# inputs.net
KiCad netlist of a schematic drawn in Altium Designer
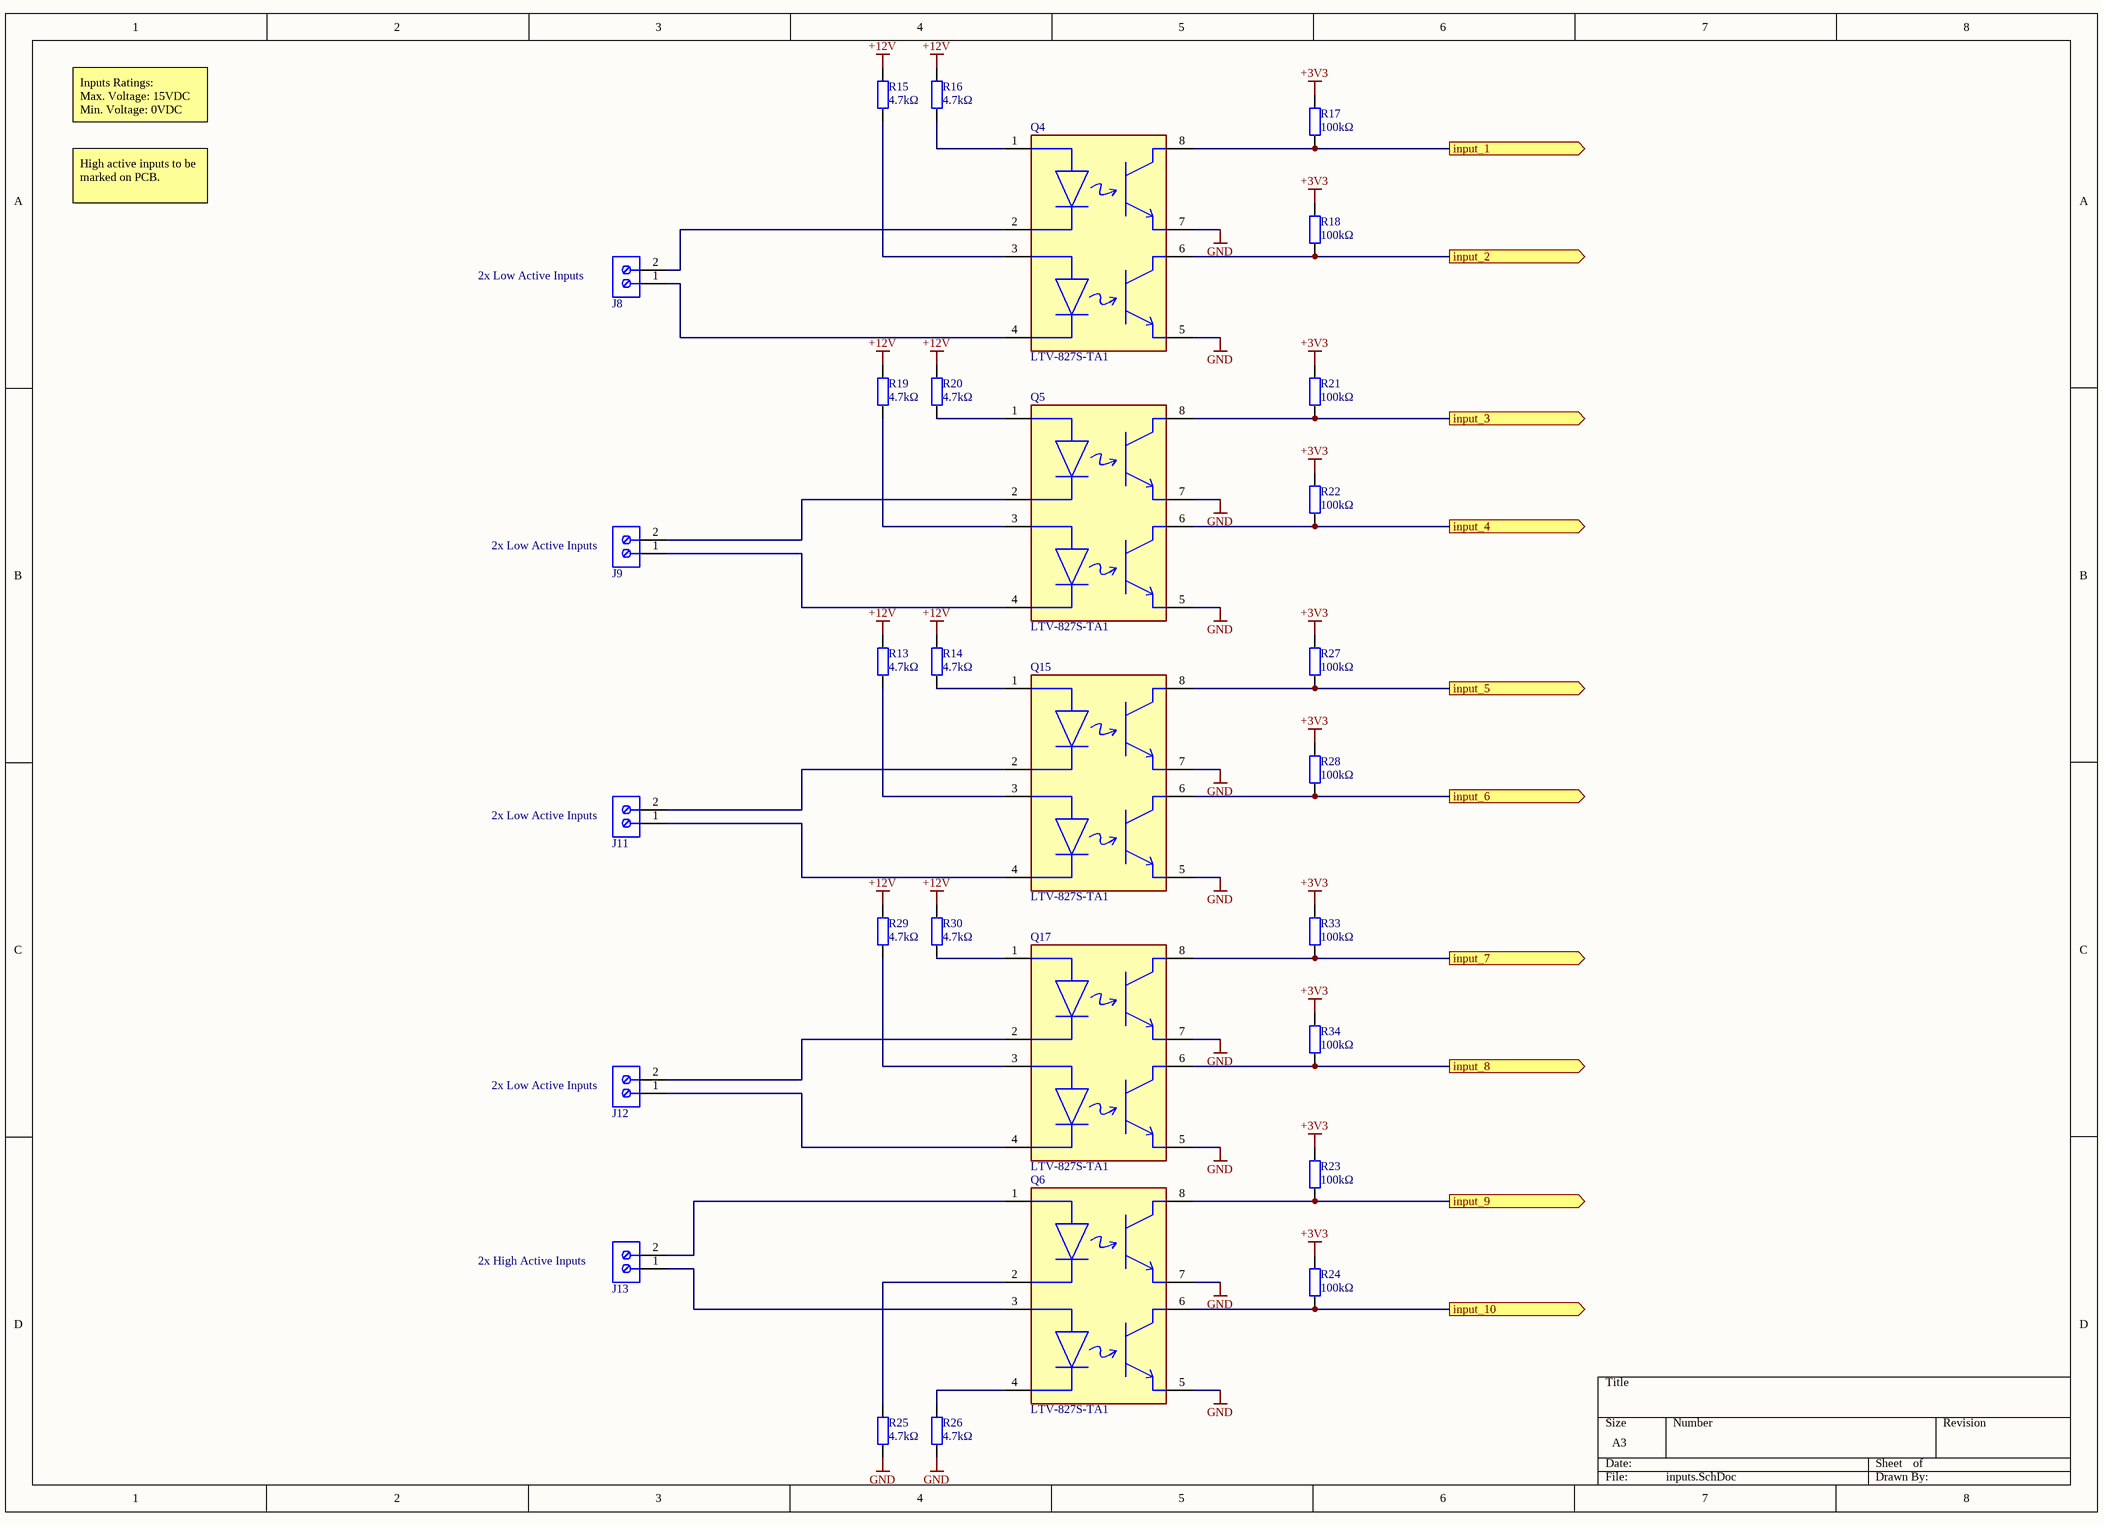
[diagram p0: inputs.SchDoc]

(export (version "E")
  (design (tool "Eeschema 10.0.6"))
  (components
    (comp (ref "J8")
      (value "282836-2")
      (footprint "TECO-282836-2_V")
      (description "Female Header, Pitch 5 mm, 1 x 2 Position, Height 10 mm, Tail Length 3.5 mm, Rohs, Bulk")
      (fields (field (name "VOLTAGE") "300V") (field (name "MANUFACTURER") "TE Connectivity"))
      (libsource (lib "Altium Content Vault") (part "CN-1P-F-TB2"))
    )
    (comp (ref "J9")
      (value "282836-2")
      (footprint "TECO-282836-2_V")
      (description "Female Header, Pitch 5 mm, 1 x 2 Position, Height 10 mm, Tail Length 3.5 mm, Rohs, Bulk")
      (fields (field (name "VOLTAGE") "300V") (field (name "MANUFACTURER") "TE Connectivity"))
      (libsource (lib "Altium Content Vault") (part "CN-1P-F-TB2"))
    )
    (comp (ref "J11")
      (value "282836-2")
      (footprint "TECO-282836-2_V")
      (description "Female Header, Pitch 5 mm, 1 x 2 Position, Height 10 mm, Tail Length 3.5 mm, Rohs, Bulk")
      (fields (field (name "VOLTAGE") "300V") (field (name "MANUFACTURER") "TE Connectivity"))
      (libsource (lib "Altium Content Vault") (part "CN-1P-F-TB2"))
    )
    (comp (ref "J12")
      (value "282836-2")
      (footprint "TECO-282836-2_V")
      (description "Female Header, Pitch 5 mm, 1 x 2 Position, Height 10 mm, Tail Length 3.5 mm, Rohs, Bulk")
      (fields (field (name "VOLTAGE") "300V") (field (name "MANUFACTURER") "TE Connectivity"))
      (libsource (lib "Altium Content Vault") (part "CN-1P-F-TB2"))
    )
    (comp (ref "J13")
      (value "282836-2")
      (footprint "TECO-282836-2_V")
      (description "Female Header, Pitch 5 mm, 1 x 2 Position, Height 10 mm, Tail Length 3.5 mm, Rohs, Bulk")
      (fields (field (name "VOLTAGE") "300V") (field (name "MANUFACTURER") "TE Connectivity"))
      (libsource (lib "Altium Content Vault") (part "CN-1P-F-TB2"))
    )
    (comp (ref "Q4")
      (value "LTV-827S-TA1")
      (footprint "FP-LTV-827S-TA1-MFG")
      (description "OPTOISOLATOR 5KV 2CH TRANS 8-SMD")
      (libsource (lib "Altium Content Vault") (part "7b7d251853f36bb38206e775f4a8ee5"))
    )
    (comp (ref "Q5")
      (value "LTV-827S-TA1")
      (footprint "FP-LTV-827S-TA1-MFG")
      (description "OPTOISOLATOR 5KV 2CH TRANS 8-SMD")
      (libsource (lib "Altium Content Vault") (part "7b7d251853f36bb38206e775f4a8ee5"))
    )
    (comp (ref "Q6")
      (value "LTV-827S-TA1")
      (footprint "FP-LTV-827S-TA1-MFG")
      (description "OPTOISOLATOR 5KV 2CH TRANS 8-SMD")
      (libsource (lib "Altium Content Vault") (part "7b7d251853f36bb38206e775f4a8ee5"))
    )
    (comp (ref "Q15")
      (value "LTV-827S-TA1")
      (footprint "FP-LTV-827S-TA1-MFG")
      (description "OPTOISOLATOR 5KV 2CH TRANS 8-SMD")
      (libsource (lib "Altium Content Vault") (part "7b7d251853f36bb38206e775f4a8ee5"))
    )
    (comp (ref "Q17")
      (value "LTV-827S-TA1")
      (footprint "FP-LTV-827S-TA1-MFG")
      (description "OPTOISOLATOR 5KV 2CH TRANS 8-SMD")
      (libsource (lib "Altium Content Vault") (part "7b7d251853f36bb38206e775f4a8ee5"))
    )
    (comp (ref "R13")
      (value "4.7kΩ")
      (footprint "RESC2013X50X30ML20T20")
      (description "Resistor")
      (libsource (lib "PCB_Project") (part "Res_0805"))
    )
    (comp (ref "R14")
      (value "4.7kΩ")
      (footprint "RESC2013X50X30ML20T20")
      (description "Resistor")
      (libsource (lib "PCB_Project") (part "Res_0805"))
    )
    (comp (ref "R15")
      (value "4.7kΩ")
      (footprint "RESC2013X50X30ML20T20")
      (description "Resistor")
      (libsource (lib "PCB_Project") (part "Res_0805"))
    )
    (comp (ref "R16")
      (value "4.7kΩ")
      (footprint "RESC2013X50X30ML20T20")
      (description "Resistor")
      (libsource (lib "PCB_Project") (part "Res_0805"))
    )
    (comp (ref "R17")
      (value "100kΩ")
      (footprint "RESC2013X50X30ML20T20")
      (description "Resistor")
      (libsource (lib "") (part "Res_0805_1"))
    )
    (comp (ref "R18")
      (value "100kΩ")
      (footprint "RESC2013X50X30ML20T20")
      (description "Resistor")
      (libsource (lib "") (part "Res_0805_1"))
    )
    (comp (ref "R19")
      (value "4.7kΩ")
      (footprint "RESC2013X50X30ML20T20")
      (description "Resistor")
      (libsource (lib "PCB_Project") (part "Res_0805"))
    )
    (comp (ref "R20")
      (value "4.7kΩ")
      (footprint "RESC2013X50X30ML20T20")
      (description "Resistor")
      (libsource (lib "PCB_Project") (part "Res_0805"))
    )
    (comp (ref "R21")
      (value "100kΩ")
      (footprint "RESC2013X50X30ML20T20")
      (description "Resistor")
      (libsource (lib "") (part "Res_0805_1"))
    )
    (comp (ref "R22")
      (value "100kΩ")
      (footprint "RESC2013X50X30ML20T20")
      (description "Resistor")
      (libsource (lib "") (part "Res_0805_1"))
    )
    (comp (ref "R23")
      (value "100kΩ")
      (footprint "RESC2013X50X30ML20T20")
      (description "Resistor")
      (libsource (lib "") (part "Res_0805_1"))
    )
    (comp (ref "R24")
      (value "100kΩ")
      (footprint "RESC2013X50X30ML20T20")
      (description "Resistor")
      (libsource (lib "") (part "Res_0805_1"))
    )
    (comp (ref "R25")
      (value "4.7kΩ")
      (footprint "RESC2013X50X30ML20T20")
      (description "Resistor")
      (libsource (lib "") (part "Res_0805_1"))
    )
    (comp (ref "R26")
      (value "4.7kΩ")
      (footprint "RESC2013X50X30ML20T20")
      (description "Resistor")
      (libsource (lib "") (part "Res_0805_1"))
    )
    (comp (ref "R27")
      (value "100kΩ")
      (footprint "RESC2013X50X30ML20T20")
      (description "Resistor")
      (libsource (lib "") (part "Res_0805_1"))
    )
    (comp (ref "R28")
      (value "100kΩ")
      (footprint "RESC2013X50X30ML20T20")
      (description "Resistor")
      (libsource (lib "") (part "Res_0805_1"))
    )
    (comp (ref "R29")
      (value "4.7kΩ")
      (footprint "RESC2013X50X30ML20T20")
      (description "Resistor")
      (libsource (lib "PCB_Project") (part "Res_0805"))
    )
    (comp (ref "R30")
      (value "4.7kΩ")
      (footprint "RESC2013X50X30ML20T20")
      (description "Resistor")
      (libsource (lib "PCB_Project") (part "Res_0805"))
    )
    (comp (ref "R33")
      (value "100kΩ")
      (footprint "RESC2013X50X30ML20T20")
      (description "Resistor")
      (libsource (lib "") (part "Res_0805_1"))
    )
    (comp (ref "R34")
      (value "100kΩ")
      (footprint "RESC2013X50X30ML20T20")
      (description "Resistor")
      (libsource (lib "") (part "Res_0805_1"))
    )
  )
  (nets
    (net (code "1") (name "+3V3") (class "Default")
      (node (ref "R17") (pin "1") (pinfunction "1_1") (pintype "passive"))
      (node (ref "R18") (pin "1") (pinfunction "1_1") (pintype "passive"))
      (node (ref "R21") (pin "1") (pinfunction "1_1") (pintype "passive"))
      (node (ref "R22") (pin "1") (pinfunction "1_1") (pintype "passive"))
      (node (ref "R23") (pin "1") (pinfunction "1_1") (pintype "passive"))
      (node (ref "R24") (pin "1") (pinfunction "1_1") (pintype "passive"))
      (node (ref "R27") (pin "1") (pinfunction "1_1") (pintype "passive"))
      (node (ref "R28") (pin "1") (pinfunction "1_1") (pintype "passive"))
      (node (ref "R33") (pin "1") (pinfunction "1_1") (pintype "passive"))
      (node (ref "R34") (pin "1") (pinfunction "1_1") (pintype "passive"))
    )
    (net (code "2") (name "+12V") (class "Default")
      (node (ref "R13") (pin "1") (pinfunction "1_1") (pintype "passive"))
      (node (ref "R14") (pin "1") (pinfunction "1_1") (pintype "passive"))
      (node (ref "R15") (pin "1") (pinfunction "1_1") (pintype "passive"))
      (node (ref "R16") (pin "1") (pinfunction "1_1") (pintype "passive"))
      (node (ref "R19") (pin "1") (pinfunction "1_1") (pintype "passive"))
      (node (ref "R20") (pin "1") (pinfunction "1_1") (pintype "passive"))
      (node (ref "R29") (pin "1") (pinfunction "1_1") (pintype "passive"))
      (node (ref "R30") (pin "1") (pinfunction "1_1") (pintype "passive"))
    )
    (net (code "3") (name "/input_1") (class "Default")
      (node (ref "Q4") (pin "8") (pinfunction "C_8") (pintype "passive"))
      (node (ref "R17") (pin "2") (pinfunction "2_2") (pintype "passive"))
    )
    (net (code "4") (name "/input_2") (class "Default")
      (node (ref "Q4") (pin "6") (pinfunction "C_6") (pintype "passive"))
      (node (ref "R18") (pin "2") (pinfunction "2_2") (pintype "passive"))
    )
    (net (code "5") (name "/input_3") (class "Default")
      (node (ref "Q5") (pin "8") (pinfunction "C_8") (pintype "passive"))
      (node (ref "R21") (pin "2") (pinfunction "2_2") (pintype "passive"))
    )
    (net (code "6") (name "/input_4") (class "Default")
      (node (ref "Q5") (pin "6") (pinfunction "C_6") (pintype "passive"))
      (node (ref "R22") (pin "2") (pinfunction "2_2") (pintype "passive"))
    )
    (net (code "7") (name "/input_5") (class "Default")
      (node (ref "Q15") (pin "8") (pinfunction "C_8") (pintype "passive"))
      (node (ref "R27") (pin "2") (pinfunction "2_2") (pintype "passive"))
    )
    (net (code "8") (name "/input_6") (class "Default")
      (node (ref "Q15") (pin "6") (pinfunction "C_6") (pintype "passive"))
      (node (ref "R28") (pin "2") (pinfunction "2_2") (pintype "passive"))
    )
    (net (code "9") (name "/input_7") (class "Default")
      (node (ref "Q17") (pin "8") (pinfunction "C_8") (pintype "passive"))
      (node (ref "R33") (pin "2") (pinfunction "2_2") (pintype "passive"))
    )
    (net (code "10") (name "/input_8") (class "Default")
      (node (ref "Q17") (pin "6") (pinfunction "C_6") (pintype "passive"))
      (node (ref "R34") (pin "2") (pinfunction "2_2") (pintype "passive"))
    )
    (net (code "11") (name "/input_9") (class "Default")
      (node (ref "Q6") (pin "8") (pinfunction "C_8") (pintype "passive"))
      (node (ref "R23") (pin "2") (pinfunction "2_2") (pintype "passive"))
    )
    (net (code "12") (name "/input_10") (class "Default")
      (node (ref "Q6") (pin "6") (pinfunction "C_6") (pintype "passive"))
      (node (ref "R24") (pin "2") (pinfunction "2_2") (pintype "passive"))
    )
    (net (code "13") (name "GND") (class "Default")
      (node (ref "Q15") (pin "5") (pinfunction "E_5") (pintype "passive"))
      (node (ref "Q15") (pin "7") (pinfunction "E_7") (pintype "passive"))
      (node (ref "Q17") (pin "5") (pinfunction "E_5") (pintype "passive"))
      (node (ref "Q17") (pin "7") (pinfunction "E_7") (pintype "passive"))
      (node (ref "Q4") (pin "5") (pinfunction "E_5") (pintype "passive"))
      (node (ref "Q4") (pin "7") (pinfunction "E_7") (pintype "passive"))
      (node (ref "Q5") (pin "5") (pinfunction "E_5") (pintype "passive"))
      (node (ref "Q5") (pin "7") (pinfunction "E_7") (pintype "passive"))
      (node (ref "Q6") (pin "5") (pinfunction "E_5") (pintype "passive"))
      (node (ref "Q6") (pin "7") (pinfunction "E_7") (pintype "passive"))
      (node (ref "R25") (pin "2") (pinfunction "2_2") (pintype "passive"))
      (node (ref "R26") (pin "2") (pinfunction "2_2") (pintype "passive"))
    )
    (net (code "14") (name "Net-(Q4-1_Anode)") (class "Default")
      (node (ref "Q4") (pin "1") (pinfunction "1_Anode_1") (pintype "passive"))
      (node (ref "R16") (pin "2") (pinfunction "2_2") (pintype "passive"))
    )
    (net (code "15") (name "Net-(Q4-1_Cathode)") (class "Default")
      (node (ref "J8") (pin "2") (pinfunction "2_2") (pintype "passive"))
      (node (ref "Q4") (pin "2") (pinfunction "1_Cathode_2") (pintype "passive"))
    )
    (net (code "16") (name "Net-(Q4-2_Anode)") (class "Default")
      (node (ref "Q4") (pin "3") (pinfunction "2_Anode_3") (pintype "passive"))
      (node (ref "R15") (pin "2") (pinfunction "2_2") (pintype "passive"))
    )
    (net (code "17") (name "Net-(Q4-2_Cathode)") (class "Default")
      (node (ref "J8") (pin "1") (pinfunction "1_1") (pintype "passive"))
      (node (ref "Q4") (pin "4") (pinfunction "2_Cathode_4") (pintype "passive"))
    )
    (net (code "18") (name "Net-(Q5-1_Anode)") (class "Default")
      (node (ref "Q5") (pin "1") (pinfunction "1_Anode_1") (pintype "passive"))
      (node (ref "R20") (pin "2") (pinfunction "2_2") (pintype "passive"))
    )
    (net (code "19") (name "Net-(Q5-1_Cathode)") (class "Default")
      (node (ref "J9") (pin "2") (pinfunction "2_2") (pintype "passive"))
      (node (ref "Q5") (pin "2") (pinfunction "1_Cathode_2") (pintype "passive"))
    )
    (net (code "20") (name "Net-(Q5-2_Anode)") (class "Default")
      (node (ref "Q5") (pin "3") (pinfunction "2_Anode_3") (pintype "passive"))
      (node (ref "R19") (pin "2") (pinfunction "2_2") (pintype "passive"))
    )
    (net (code "21") (name "Net-(Q5-2_Cathode)") (class "Default")
      (node (ref "J9") (pin "1") (pinfunction "1_1") (pintype "passive"))
      (node (ref "Q5") (pin "4") (pinfunction "2_Cathode_4") (pintype "passive"))
    )
    (net (code "22") (name "Net-(Q6-1_Anode)") (class "Default")
      (node (ref "J13") (pin "2") (pinfunction "2_2") (pintype "passive"))
      (node (ref "Q6") (pin "1") (pinfunction "1_Anode_1") (pintype "passive"))
    )
    (net (code "23") (name "Net-(Q6-1_Cathode)") (class "Default")
      (node (ref "Q6") (pin "2") (pinfunction "1_Cathode_2") (pintype "passive"))
      (node (ref "R25") (pin "1") (pinfunction "1_1") (pintype "passive"))
    )
    (net (code "24") (name "Net-(Q6-2_Anode)") (class "Default")
      (node (ref "J13") (pin "1") (pinfunction "1_1") (pintype "passive"))
      (node (ref "Q6") (pin "3") (pinfunction "2_Anode_3") (pintype "passive"))
    )
    (net (code "25") (name "Net-(Q6-2_Cathode)") (class "Default")
      (node (ref "Q6") (pin "4") (pinfunction "2_Cathode_4") (pintype "passive"))
      (node (ref "R26") (pin "1") (pinfunction "1_1") (pintype "passive"))
    )
    (net (code "26") (name "Net-(Q15-1_Anode)") (class "Default")
      (node (ref "Q15") (pin "1") (pinfunction "1_Anode_1") (pintype "passive"))
      (node (ref "R14") (pin "2") (pinfunction "2_2") (pintype "passive"))
    )
    (net (code "27") (name "Net-(Q15-1_Cathode)") (class "Default")
      (node (ref "J11") (pin "2") (pinfunction "2_2") (pintype "passive"))
      (node (ref "Q15") (pin "2") (pinfunction "1_Cathode_2") (pintype "passive"))
    )
    (net (code "28") (name "Net-(Q15-2_Anode)") (class "Default")
      (node (ref "Q15") (pin "3") (pinfunction "2_Anode_3") (pintype "passive"))
      (node (ref "R13") (pin "2") (pinfunction "2_2") (pintype "passive"))
    )
    (net (code "29") (name "Net-(Q15-2_Cathode)") (class "Default")
      (node (ref "J11") (pin "1") (pinfunction "1_1") (pintype "passive"))
      (node (ref "Q15") (pin "4") (pinfunction "2_Cathode_4") (pintype "passive"))
    )
    (net (code "30") (name "Net-(Q17-1_Anode)") (class "Default")
      (node (ref "Q17") (pin "1") (pinfunction "1_Anode_1") (pintype "passive"))
      (node (ref "R30") (pin "2") (pinfunction "2_2") (pintype "passive"))
    )
    (net (code "31") (name "Net-(Q17-1_Cathode)") (class "Default")
      (node (ref "J12") (pin "2") (pinfunction "2_2") (pintype "passive"))
      (node (ref "Q17") (pin "2") (pinfunction "1_Cathode_2") (pintype "passive"))
    )
    (net (code "32") (name "Net-(Q17-2_Anode)") (class "Default")
      (node (ref "Q17") (pin "3") (pinfunction "2_Anode_3") (pintype "passive"))
      (node (ref "R29") (pin "2") (pinfunction "2_2") (pintype "passive"))
    )
    (net (code "33") (name "Net-(Q17-2_Cathode)") (class "Default")
      (node (ref "J12") (pin "1") (pinfunction "1_1") (pintype "passive"))
      (node (ref "Q17") (pin "4") (pinfunction "2_Cathode_4") (pintype "passive"))
    )
  )
)
